# 3_-MCU.net
KiCad netlist of a schematic drawn in Altium Designer
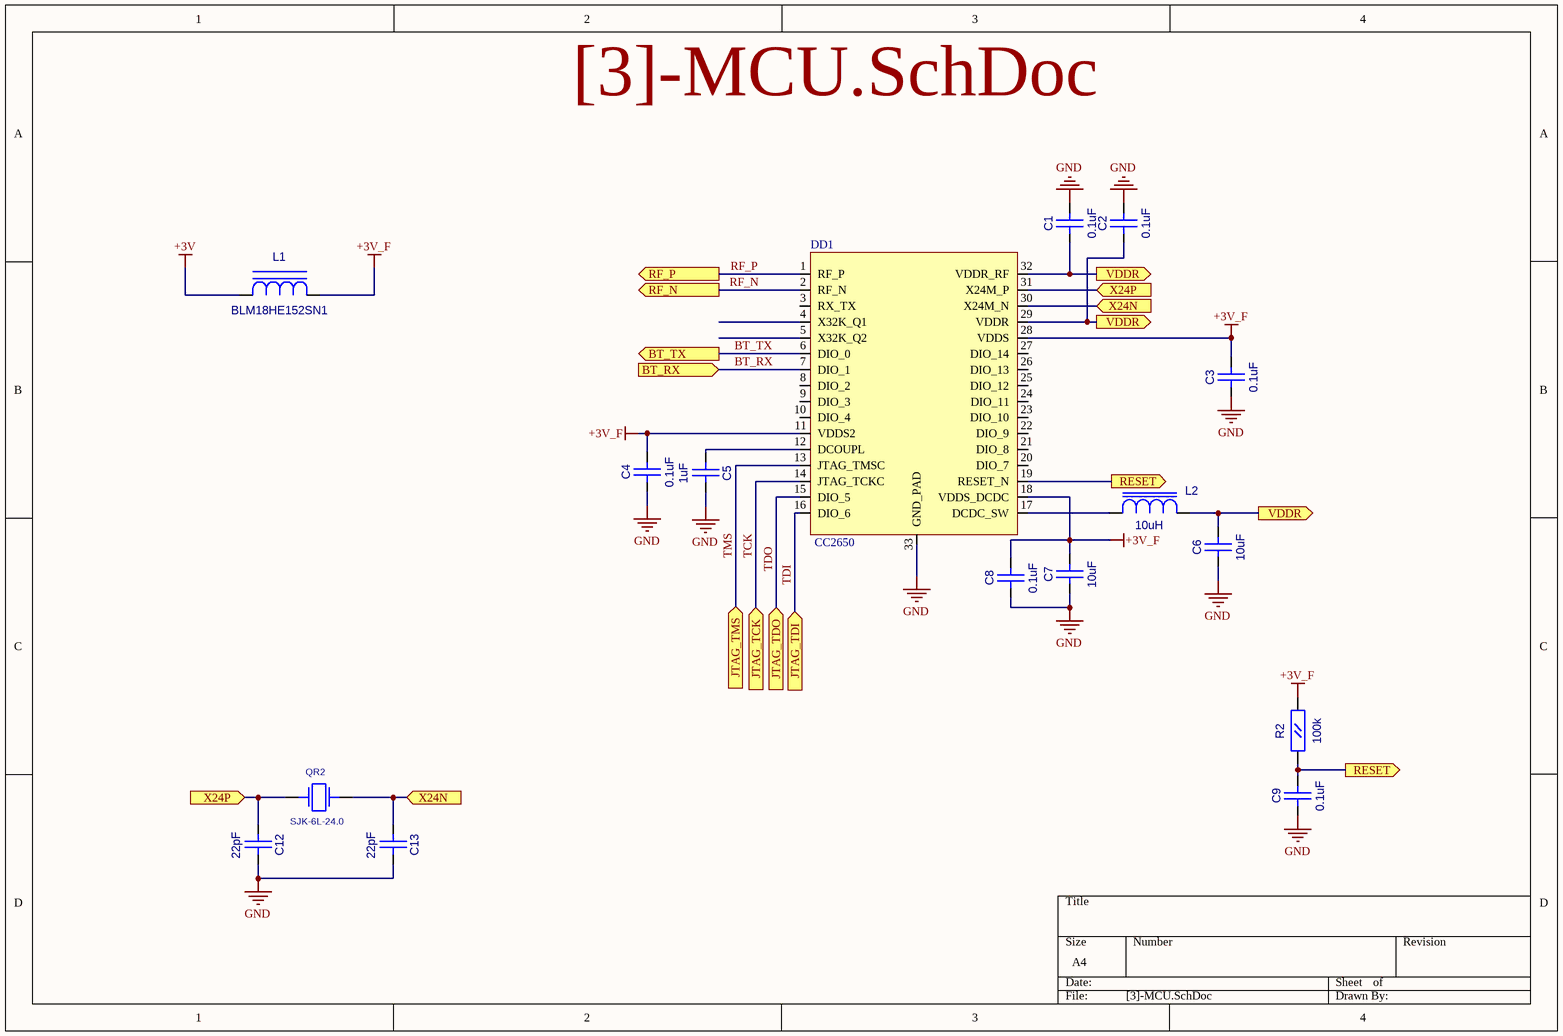
[diagram p0: [3]-MCU.SchDoc]

(export (version "E")
  (design (tool "Eeschema 10.0.6"))
  (components
    (comp (ref "C1")
      (value "0.1uF")
      (footprint "CC0603")
      (description "CC0603")
      (libsource (lib "gprs_modem_2") (part "CC0603"))
    )
    (comp (ref "C2")
      (value "0.1uF")
      (footprint "CC0603")
      (description "CC0603")
      (libsource (lib "gprs_modem_2") (part "CC0603"))
    )
    (comp (ref "C3")
      (value "0.1uF")
      (footprint "CC0603")
      (description "CC0603")
      (libsource (lib "gprs_modem_2") (part "CC0603"))
    )
    (comp (ref "C4")
      (value "0.1uF")
      (footprint "CC0603")
      (description "CC0603")
      (libsource (lib "gprs_modem_2") (part "CC0603"))
    )
    (comp (ref "C5")
      (value "1uF")
      (footprint "CC0603")
      (description "CC0603")
      (libsource (lib "gprs_modem_2") (part "CC0603"))
    )
    (comp (ref "C6")
      (value "10uF")
      (footprint "CC0805")
      (description "CC0805")
      (libsource (lib "gprs_modem_2") (part "CC0805"))
    )
    (comp (ref "C7")
      (value "10uF")
      (footprint "CC0805")
      (description "CC0805")
      (libsource (lib "gprs_modem_2") (part "CC0805"))
    )
    (comp (ref "C8")
      (value "0.1uF")
      (footprint "CC0603")
      (description "CC0603")
      (libsource (lib "gprs_modem_2") (part "CC0603"))
    )
    (comp (ref "C9")
      (value "0.1uF")
      (footprint "CC0603")
      (description "CC0603")
      (libsource (lib "gprs_modem_2") (part "CC0603"))
    )
    (comp (ref "C12")
      (value "22pF")
      (footprint "CC0603")
      (description "CC0603")
      (libsource (lib "gprs_modem_2") (part "CC0603"))
    )
    (comp (ref "C13")
      (value "22pF")
      (footprint "CC0603")
      (description "CC0603")
      (libsource (lib "gprs_modem_2") (part "CC0603"))
    )
    (comp (ref "DD1")
      (value "CC2650")
      (footprint "QFN32_TI")
      (description "CC2650RHBT")
      (libsource (lib "gprs_modem_2") (part "CC2650RHB"))
    )
    (comp (ref "L1")
      (value "BLM18HE152SN1")
      (footprint "L0603")
      (description "L0603")
      (libsource (lib "gprs_modem_2") (part "L0603"))
    )
    (comp (ref "L2")
      (value "10uH")
      (footprint "RC0805")
      (description "L0805")
      (libsource (lib "gprs_modem_2") (part "L0805"))
    )
    (comp (ref "QR2")
      (value "SJK-6L-24.0")
      (footprint "AC5032_2")
      (description "AC5032/2")
      (libsource (lib "gprs_modem_2") (part "AC5032_2"))
    )
    (comp (ref "R2")
      (value "100k")
      (footprint "RC0603")
      (description "RC0603")
      (libsource (lib "gprs_modem_2") (part "RC0603"))
    )
  )
  (nets
    (net (code "1") (name "+3V") (class "Default")
      (node (ref "L1") (pin "1") (pinfunction "A_1") (pintype "passive"))
    )
    (net (code "2") (name "+3V_F") (class "Default")
      (node (ref "C3") (pin "2") (pinfunction "B_2") (pintype "passive"))
      (node (ref "C4") (pin "2") (pinfunction "B_2") (pintype "passive"))
      (node (ref "C7") (pin "2") (pinfunction "B_2") (pintype "passive"))
      (node (ref "C8") (pin "2") (pinfunction "B_2") (pintype "passive"))
      (node (ref "DD1") (pin "11") (pinfunction "VDDS2_11") (pintype "passive"))
      (node (ref "DD1") (pin "18") (pinfunction "VDDS_DCDC_18") (pintype "passive"))
      (node (ref "DD1") (pin "28") (pinfunction "VDDS_28") (pintype "passive"))
      (node (ref "L1") (pin "2") (pinfunction "C_2") (pintype "passive"))
      (node (ref "R2") (pin "2") (pinfunction "B_2") (pintype "passive"))
    )
    (net (code "3") (name "/BT_RX") (class "Default")
      (node (ref "DD1") (pin "7") (pinfunction "DIO_1_7") (pintype "passive"))
    )
    (net (code "4") (name "/BT_TX") (class "Default")
      (node (ref "DD1") (pin "6") (pinfunction "DIO_0_6") (pintype "passive"))
    )
    (net (code "5") (name "/RESET") (class "Default")
      (node (ref "C9") (pin "2") (pinfunction "B_2") (pintype "passive"))
      (node (ref "DD1") (pin "19") (pinfunction "RESET_N_19") (pintype "passive"))
      (node (ref "R2") (pin "1") (pinfunction "A_1") (pintype "passive"))
    )
    (net (code "6") (name "/RF_N") (class "Default")
      (node (ref "DD1") (pin "2") (pinfunction "RF_N_2") (pintype "passive"))
    )
    (net (code "7") (name "/RF_P") (class "Default")
      (node (ref "DD1") (pin "1") (pinfunction "RF_P_1") (pintype "passive"))
    )
    (net (code "8") (name "/TCK") (class "Default")
      (node (ref "DD1") (pin "14") (pinfunction "JTAG_TCKC_14") (pintype "passive"))
    )
    (net (code "9") (name "/TDI") (class "Default")
      (node (ref "DD1") (pin "16") (pinfunction "DIO_6_16") (pintype "passive"))
    )
    (net (code "10") (name "/TDO") (class "Default")
      (node (ref "DD1") (pin "15") (pinfunction "DIO_5_15") (pintype "passive"))
    )
    (net (code "11") (name "/TMS") (class "Default")
      (node (ref "DD1") (pin "13") (pinfunction "JTAG_TMSC_13") (pintype "passive"))
    )
    (net (code "12") (name "/VDDR") (class "Default")
      (node (ref "C1") (pin "1") (pinfunction "A_1") (pintype "passive"))
      (node (ref "C2") (pin "1") (pinfunction "A_1") (pintype "passive"))
      (node (ref "C6") (pin "2") (pinfunction "B_2") (pintype "passive"))
      (node (ref "DD1") (pin "29") (pinfunction "VDDR_29") (pintype "passive"))
      (node (ref "DD1") (pin "32") (pinfunction "VDDR_RF_32") (pintype "passive"))
      (node (ref "L2") (pin "2") (pinfunction "B_2") (pintype "passive"))
    )
    (net (code "13") (name "/X24N") (class "Default")
      (node (ref "C13") (pin "1") (pinfunction "A_1") (pintype "passive"))
      (node (ref "DD1") (pin "30") (pinfunction "X24M_N_30") (pintype "passive"))
      (node (ref "QR2") (pin "2") (pintype "passive"))
    )
    (net (code "14") (name "/X24P") (class "Default")
      (node (ref "C12") (pin "1") (pinfunction "A_1") (pintype "passive"))
      (node (ref "DD1") (pin "31") (pinfunction "X24M_P_31") (pintype "passive"))
      (node (ref "QR2") (pin "1") (pintype "passive"))
    )
    (net (code "15") (name "GND") (class "Default")
      (node (ref "C1") (pin "2") (pinfunction "B_2") (pintype "passive"))
      (node (ref "C12") (pin "2") (pinfunction "B_2") (pintype "passive"))
      (node (ref "C13") (pin "2") (pinfunction "B_2") (pintype "passive"))
      (node (ref "C2") (pin "2") (pinfunction "B_2") (pintype "passive"))
      (node (ref "C3") (pin "1") (pinfunction "A_1") (pintype "passive"))
      (node (ref "C4") (pin "1") (pinfunction "A_1") (pintype "passive"))
      (node (ref "C5") (pin "2") (pinfunction "B_2") (pintype "passive"))
      (node (ref "C6") (pin "1") (pinfunction "A_1") (pintype "passive"))
      (node (ref "C7") (pin "1") (pinfunction "A_1") (pintype "passive"))
      (node (ref "C8") (pin "1") (pinfunction "A_1") (pintype "passive"))
      (node (ref "C9") (pin "1") (pinfunction "A_1") (pintype "passive"))
      (node (ref "DD1") (pin "33") (pinfunction "GND_PAD_33") (pintype "passive"))
    )
    (net (code "16") (name "Net-(C5-A)") (class "Default")
      (node (ref "C5") (pin "1") (pinfunction "A_1") (pintype "passive"))
      (node (ref "DD1") (pin "12") (pinfunction "DCOUPL_12") (pintype "passive"))
    )
    (net (code "17") (name "Net-(DD1-DCDC_SW)") (class "Default")
      (node (ref "DD1") (pin "17") (pinfunction "DCDC_SW_17") (pintype "passive"))
      (node (ref "L2") (pin "1") (pinfunction "A_1") (pintype "passive"))
    )
    (net (code "18") (name "unconnected-(DD1-DIO_2-Pad8)") (class "Default")
      (node (ref "DD1") (pin "8") (pinfunction "DIO_2_8") (pintype "passive"))
    )
    (net (code "19") (name "unconnected-(DD1-DIO_3-Pad9)") (class "Default")
      (node (ref "DD1") (pin "9") (pinfunction "DIO_3_9") (pintype "passive"))
    )
    (net (code "20") (name "unconnected-(DD1-DIO_4-Pad10)") (class "Default")
      (node (ref "DD1") (pin "10") (pinfunction "DIO_4_10") (pintype "passive"))
    )
    (net (code "21") (name "unconnected-(DD1-DIO_7-Pad20)") (class "Default")
      (node (ref "DD1") (pin "20") (pinfunction "DIO_7_20") (pintype "passive"))
    )
    (net (code "22") (name "unconnected-(DD1-DIO_8-Pad21)") (class "Default")
      (node (ref "DD1") (pin "21") (pinfunction "DIO_8_21") (pintype "passive"))
    )
    (net (code "23") (name "unconnected-(DD1-DIO_9-Pad22)") (class "Default")
      (node (ref "DD1") (pin "22") (pinfunction "DIO_9_22") (pintype "passive"))
    )
    (net (code "24") (name "unconnected-(DD1-DIO_10-Pad23)") (class "Default")
      (node (ref "DD1") (pin "23") (pinfunction "DIO_10_23") (pintype "passive"))
    )
    (net (code "25") (name "unconnected-(DD1-DIO_11-Pad24)") (class "Default")
      (node (ref "DD1") (pin "24") (pinfunction "DIO_11_24") (pintype "passive"))
    )
    (net (code "26") (name "unconnected-(DD1-DIO_12-Pad25)") (class "Default")
      (node (ref "DD1") (pin "25") (pinfunction "DIO_12_25") (pintype "passive"))
    )
    (net (code "27") (name "unconnected-(DD1-DIO_13-Pad26)") (class "Default")
      (node (ref "DD1") (pin "26") (pinfunction "DIO_13_26") (pintype "passive"))
    )
    (net (code "28") (name "unconnected-(DD1-DIO_14-Pad27)") (class "Default")
      (node (ref "DD1") (pin "27") (pinfunction "DIO_14_27") (pintype "passive"))
    )
    (net (code "29") (name "unconnected-(DD1-RX_TX-Pad3)") (class "Default")
      (node (ref "DD1") (pin "3") (pinfunction "RX_TX_3") (pintype "passive"))
    )
    (net (code "30") (name "unconnected-(DD1-X32K_Q1-Pad4)") (class "Default")
      (node (ref "DD1") (pin "4") (pinfunction "X32K_Q1_4") (pintype "passive"))
    )
    (net (code "31") (name "unconnected-(DD1-X32K_Q2-Pad5)") (class "Default")
      (node (ref "DD1") (pin "5") (pinfunction "X32K_Q2_5") (pintype "passive"))
    )
  )
)
